# 8085_shadow.net
KiCad netlist of a schematic drawn in EAGLE
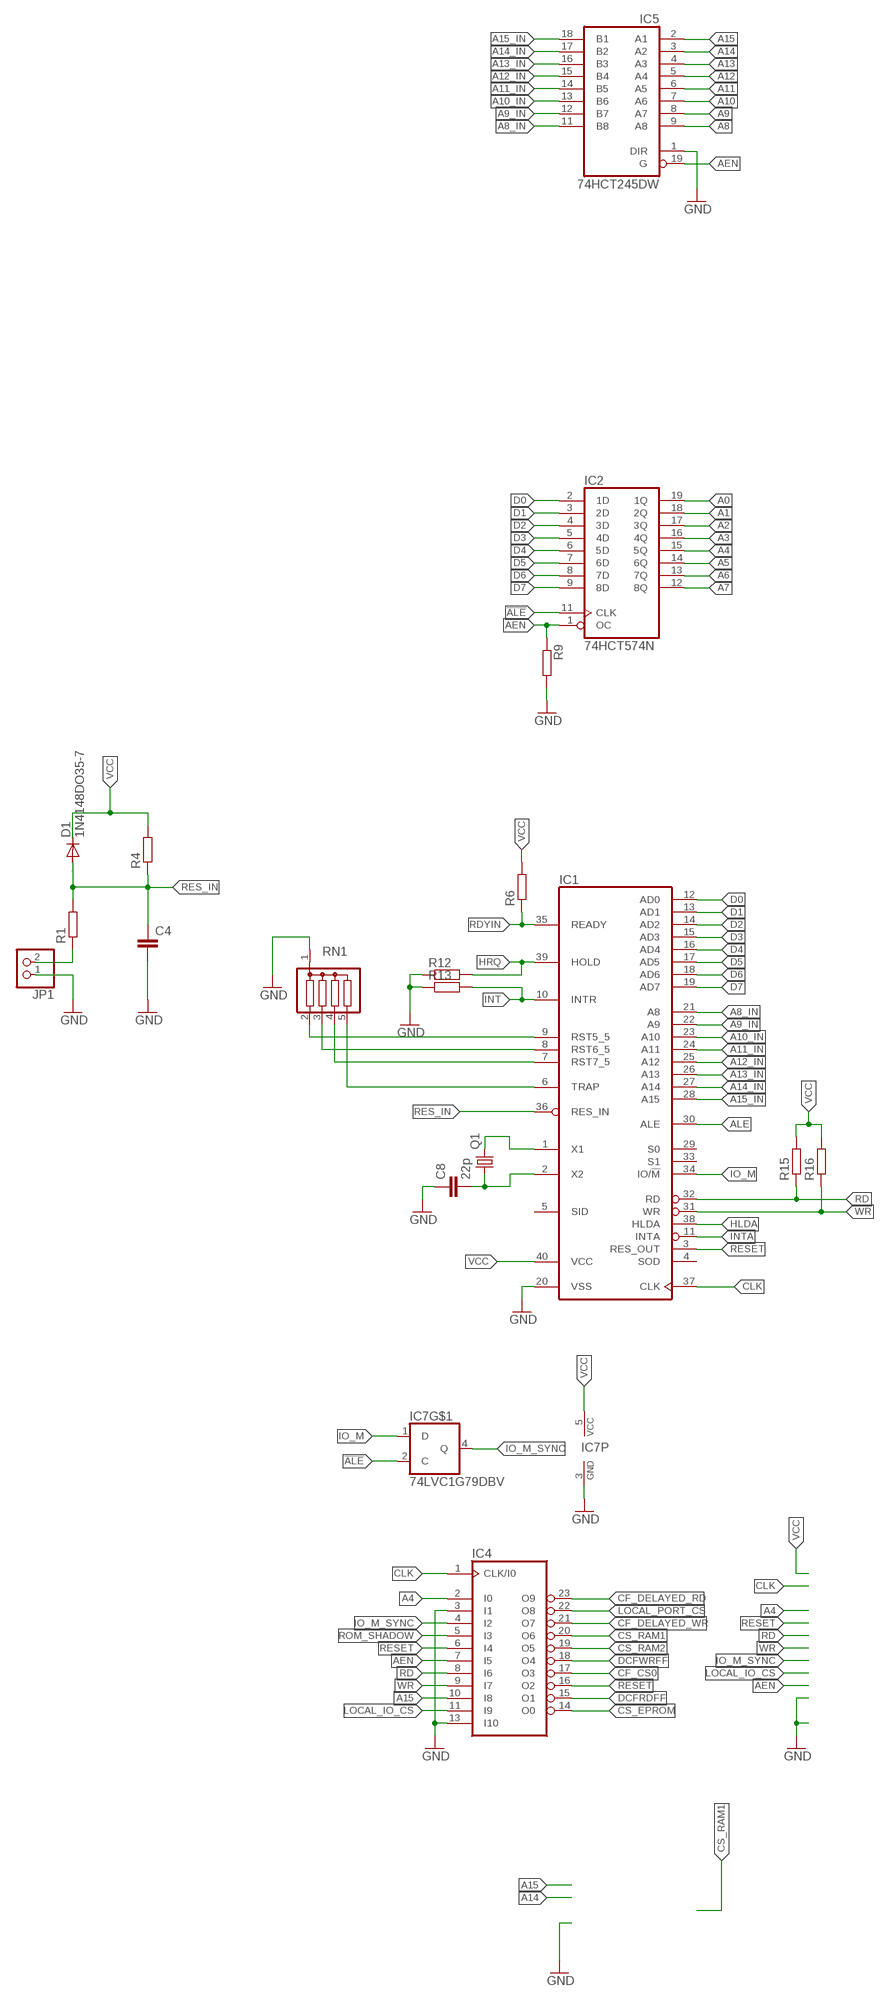
[diagram p0: schematic, sheet 1, part 1 of 3]
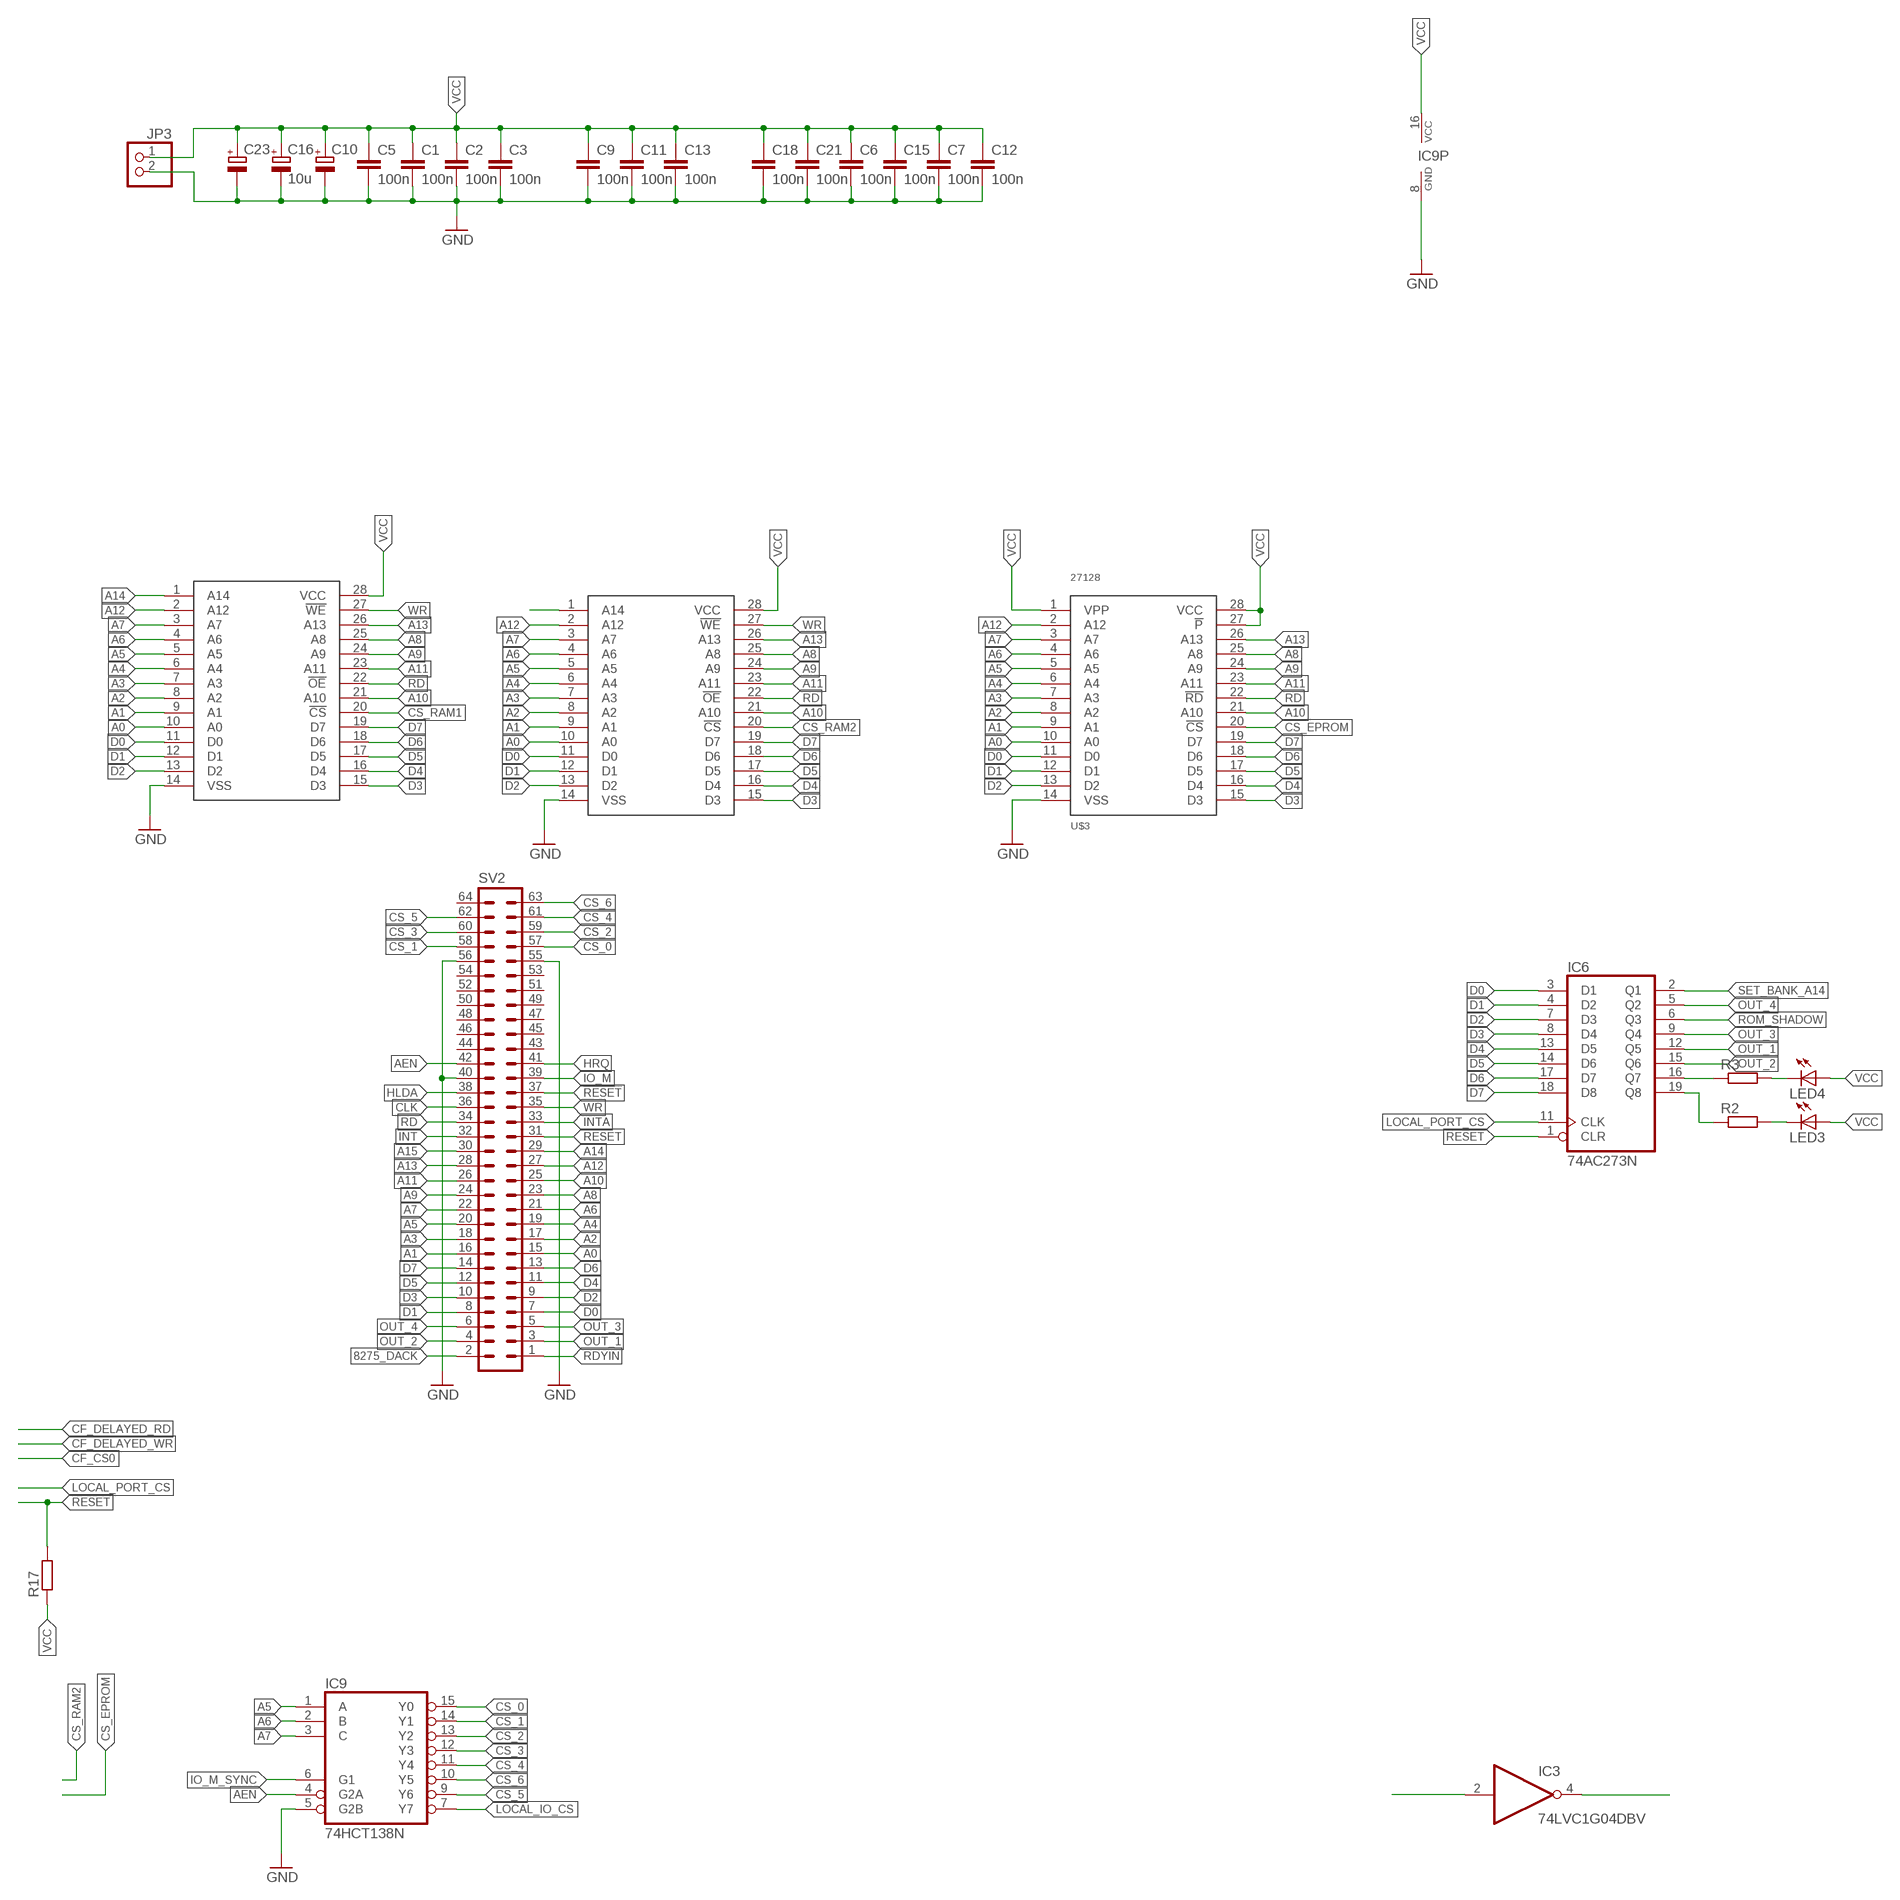
[diagram p1: schematic, sheet 1, part 2 of 3]
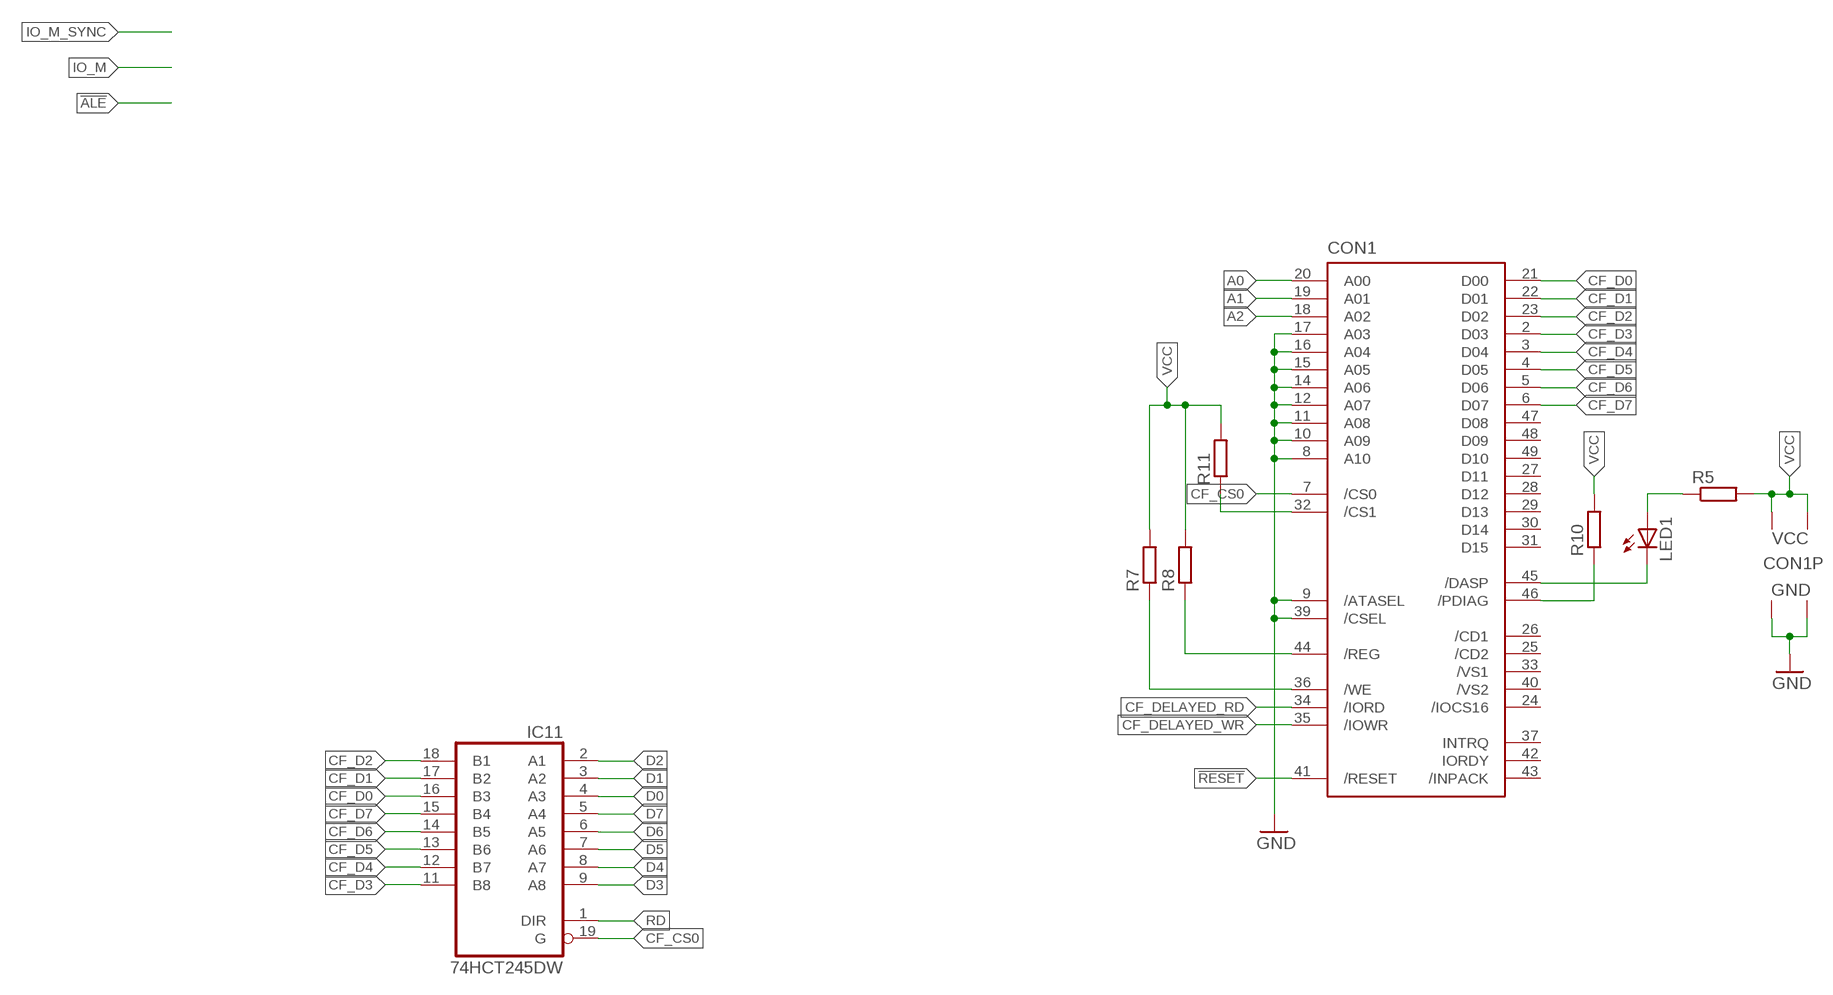
[diagram p2: schematic, sheet 1, part 3 of 3]

(export (version "E")
  (design (tool "Eeschema 10.0.6"))
  (components
    (comp (ref "C1")
      (value "100n")
      (footprint "eagle-import:C0805")
      (libsource (lib "eagle-import") (part "C-EUC0805"))
    )
    (comp (ref "C2")
      (value "100n")
      (footprint "eagle-import:C0805")
      (libsource (lib "eagle-import") (part "C-EUC0805"))
    )
    (comp (ref "C3")
      (value "100n")
      (footprint "eagle-import:C0805")
      (libsource (lib "eagle-import") (part "C-EUC0805"))
    )
    (comp (ref "C4")
      (value "C-EUC0603")
      (footprint "eagle-import:C0603")
      (libsource (lib "eagle-import") (part "C-EUC0603"))
    )
    (comp (ref "C5")
      (value "100n")
      (footprint "eagle-import:C0603")
      (libsource (lib "eagle-import") (part "C-EUC0603"))
    )
    (comp (ref "C6")
      (value "100n")
      (footprint "eagle-import:C0603")
      (libsource (lib "eagle-import") (part "C-EUC0603"))
    )
    (comp (ref "C7")
      (value "100n")
      (footprint "eagle-import:C0603")
      (libsource (lib "eagle-import") (part "C-EUC0603"))
    )
    (comp (ref "C8")
      (value "22p")
      (footprint "eagle-import:C0603")
      (libsource (lib "eagle-import") (part "C-EUC0603"))
    )
    (comp (ref "C9")
      (value "100n")
      (footprint "eagle-import:C1206")
      (libsource (lib "eagle-import") (part "C-EUC1206"))
    )
    (comp (ref "C10")
      (value "CPOL-EUE5-10.5")
      (footprint "eagle-import:E5-10,5")
      (libsource (lib "eagle-import") (part "CPOL-EUE5-10.5"))
    )
    (comp (ref "C11")
      (value "100n")
      (footprint "eagle-import:C0805")
      (libsource (lib "eagle-import") (part "C-EUC0805"))
    )
    (comp (ref "C12")
      (value "100n")
      (footprint "eagle-import:C0805")
      (libsource (lib "eagle-import") (part "C-EUC0805"))
    )
    (comp (ref "C13")
      (value "100n")
      (footprint "eagle-import:C0805")
      (libsource (lib "eagle-import") (part "C-EUC0805"))
    )
    (comp (ref "C15")
      (value "100n")
      (footprint "eagle-import:C0603")
      (libsource (lib "eagle-import") (part "C-EUC0603"))
    )
    (comp (ref "C16")
      (value "10u")
      (footprint "eagle-import:SMC_B")
      (libsource (lib "eagle-import") (part "CPOL-EUSMCB"))
    )
    (comp (ref "C18")
      (value "100n")
      (footprint "eagle-import:C0603")
      (libsource (lib "eagle-import") (part "C-EUC0603"))
    )
    (comp (ref "C21")
      (value "100n")
      (footprint "eagle-import:C0603")
      (libsource (lib "eagle-import") (part "C-EUC0603"))
    )
    (comp (ref "C23")
      (value "CPOL-EUE5-10.5")
      (footprint "eagle-import:E5-10,5")
      (libsource (lib "eagle-import") (part "CPOL-EUE5-10.5"))
    )
    (comp (ref "CON1")
      (value "CF-CARD-IDE_MODE")
      (footprint "eagle-import:MI20-50PD-SF")
      (libsource (lib "eagle-import") (part "CF-CARD-IDE_MODE"))
    )
    (comp (ref "D1")
      (value "1N4148DO35-7")
      (footprint "eagle-import:DO35-7")
      (libsource (lib "eagle-import") (part "1N4148DO35-7"))
    )
    (comp (ref "IC1")
      (value "8085")
      (footprint "eagle-import:DIL40")
      (libsource (lib "eagle-import") (part "8085"))
    )
    (comp (ref "IC2")
      (value "74HCT574N")
      (footprint "eagle-import:DIL20")
      (libsource (lib "eagle-import") (part "74574NHCT"))
    )
    (comp (ref "IC3")
      (value "74LVC1G04DBV")
      (footprint "eagle-import:SOT23-5")
      (libsource (lib "eagle-import") (part "741G04DBVLVC"))
    )
    (comp (ref "IC4")
      (value "22V10")
      (footprint "eagle-import:DIL24-3")
      (fields (field (name "MPN") "GAL22V10D-7LPN"))
      (libsource (lib "eagle-import") (part "22V10"))
    )
    (comp (ref "IC5")
      (value "74HCT245DW")
      (footprint "eagle-import:SO20W")
      (libsource (lib "eagle-import") (part "74245DWHCT"))
    )
    (comp (ref "IC6")
      (value "74AC273N")
      (footprint "eagle-import:DIL20")
      (libsource (lib "eagle-import") (part "74273NAC"))
    )
    (comp (ref "IC7")
      (value "74LVC1G79DBV")
      (footprint "eagle-import:SOT23-5")
      (libsource (lib "eagle-import") (part "741G79DBVLVC"))
    )
    (comp (ref "IC9")
      (value "74HCT138N")
      (footprint "eagle-import:DIL16")
      (libsource (lib "eagle-import") (part "74138NHCT"))
    )
    (comp (ref "IC11")
      (value "74HCT245DW")
      (footprint "eagle-import:SO20W")
      (libsource (lib "eagle-import") (part "74245DWHCT"))
    )
    (comp (ref "JP1")
      (value "PINHD-1X2")
      (footprint "eagle-import:1X02")
      (libsource (lib "eagle-import") (part "PINHD-1X2"))
    )
    (comp (ref "JP3")
      (value "PINHD-1X2")
      (footprint "eagle-import:1X02")
      (libsource (lib "eagle-import") (part "PINHD-1X2"))
    )
    (comp (ref "LED1")
      (value "LED5MM")
      (footprint "eagle-import:LED5MM")
      (libsource (lib "eagle-import") (part "LED5MM"))
    )
    (comp (ref "LED3")
      (value "LED5MM")
      (footprint "eagle-import:LED5MM")
      (libsource (lib "eagle-import") (part "LED5MM"))
    )
    (comp (ref "LED4")
      (value "LED5MM")
      (footprint "eagle-import:LED5MM")
      (libsource (lib "eagle-import") (part "LED5MM"))
    )
    (comp (ref "Q1")
      (value "CRYSTALHC49S")
      (footprint "eagle-import:HC49_S")
      (libsource (lib "eagle-import") (part "CRYSTALHC49S"))
    )
    (comp (ref "R1")
      (value "R-EU_0204/5")
      (footprint "eagle-import:0204_5")
      (libsource (lib "eagle-import") (part "R-EU_0204/5"))
    )
    (comp (ref "R2")
      (value "R-EU_R1206")
      (footprint "eagle-import:R1206")
      (libsource (lib "eagle-import") (part "R-EU_R1206"))
    )
    (comp (ref "R3")
      (value "R-EU_R1206")
      (footprint "eagle-import:R1206")
      (libsource (lib "eagle-import") (part "R-EU_R1206"))
    )
    (comp (ref "R4")
      (value "R-EU_0204/7")
      (footprint "eagle-import:0204_7")
      (libsource (lib "eagle-import") (part "R-EU_0204/7"))
    )
    (comp (ref "R5")
      (value "R-EU_R0603")
      (footprint "eagle-import:R0603")
      (libsource (lib "eagle-import") (part "R-EU_R0603"))
    )
    (comp (ref "R6")
      (value "R-EU_0204/5")
      (footprint "eagle-import:0204_5")
      (libsource (lib "eagle-import") (part "R-EU_0204/5"))
    )
    (comp (ref "R7")
      (value "R-EU_0207/10")
      (footprint "eagle-import:0207_10")
      (libsource (lib "eagle-import") (part "R-EU_0207/10"))
    )
    (comp (ref "R8")
      (value "R-EU_0207/12")
      (footprint "eagle-import:0207_12")
      (libsource (lib "eagle-import") (part "R-EU_0207/12"))
    )
    (comp (ref "R9")
      (value "R-EU_R0603")
      (footprint "eagle-import:R0603")
      (libsource (lib "eagle-import") (part "R-EU_R0603"))
    )
    (comp (ref "R10")
      (value "R-EU_0207/12")
      (footprint "eagle-import:0207_12")
      (libsource (lib "eagle-import") (part "R-EU_0207/12"))
    )
    (comp (ref "R11")
      (value "R-EU_0207/10")
      (footprint "eagle-import:0207_10")
      (libsource (lib "eagle-import") (part "R-EU_0207/10"))
    )
    (comp (ref "R12")
      (value "R-EU_R0603")
      (footprint "eagle-import:R0603")
      (libsource (lib "eagle-import") (part "R-EU_R0603"))
    )
    (comp (ref "R13")
      (value "R-EU_R0603")
      (footprint "eagle-import:R0603")
      (libsource (lib "eagle-import") (part "R-EU_R0603"))
    )
    (comp (ref "R15")
      (value "R-EU_0204/7")
      (footprint "eagle-import:0204_7")
      (libsource (lib "eagle-import") (part "R-EU_0204/7"))
    )
    (comp (ref "R16")
      (value "R-EU_0204/7")
      (footprint "eagle-import:0204_7")
      (libsource (lib "eagle-import") (part "R-EU_0204/7"))
    )
    (comp (ref "R17")
      (value "R-EU_0204/7")
      (footprint "eagle-import:0204_7")
      (libsource (lib "eagle-import") (part "R-EU_0204/7"))
    )
    (comp (ref "RN1")
      (value "G04R")
      (footprint "eagle-import:SIL5")
      (libsource (lib "eagle-import") (part "G04R"))
    )
    (comp (ref "SV2")
      (value "ML64L")
      (footprint "eagle-import:ML64L")
      (libsource (lib "eagle-import") (part "ML64L"))
    )
    (comp (ref "U$2")
      (value "62256")
      (footprint "eagle-import:DIL28-6")
      (libsource (lib "eagle-import") (part "62256"))
    )
    (comp (ref "U$3")
      (value "27128")
      (footprint "eagle-import:DIL28")
      (libsource (lib "eagle-import") (part "27128"))
    )
    (comp (ref "U$4")
      (value "62256")
      (footprint "eagle-import:DIL28-6")
      (libsource (lib "eagle-import") (part "62256"))
    )
  )
  (nets
    (net (code "1") (name "/~{ALE}") (class "Default")
      (node (ref "IC2") (pin "11") (pinfunction "CLK_11") (pintype "input"))
      (node (ref "IC3") (pin "4") (pinfunction "O_4") (pintype "output"))
      (node (ref "IC7") (pin "2") (pinfunction "C_2") (pintype "input"))
    )
    (net (code "2") (name "/~{RESET}") (class "Default")
      (node (ref "CON1") (pin "41") (pinfunction "/RESET_41") (pintype "input"))
      (node (ref "IC4") (pin "16") (pinfunction "O2_16") (pintype "bidirectional"))
      (node (ref "IC6") (pin "1") (pinfunction "CLR_1") (pintype "input"))
      (node (ref "R17") (pin "2") (pinfunction "2_2") (pintype "passive"))
      (node (ref "SV2") (pin "37") (pinfunction "37_37") (pintype "passive"))
    )
    (net (code "3") (name "8275_DACK") (class "Default")
      (node (ref "SV2") (pin "2") (pinfunction "2_2") (pintype "passive"))
    )
    (net (code "4") (name "A0") (class "Default")
      (node (ref "CON1") (pin "20") (pinfunction "A00_20") (pintype "input"))
      (node (ref "IC2") (pin "19") (pinfunction "1Q_19") (pintype "tri_state"))
      (node (ref "SV2") (pin "15") (pinfunction "15_15") (pintype "passive"))
      (node (ref "U$2") (pin "10") (pinfunction "A0_10") (pintype "bidirectional"))
      (node (ref "U$3") (pin "10") (pinfunction "A0_10") (pintype "bidirectional"))
      (node (ref "U$4") (pin "10") (pinfunction "A0_10") (pintype "bidirectional"))
    )
    (net (code "5") (name "A1") (class "Default")
      (node (ref "CON1") (pin "19") (pinfunction "A01_19") (pintype "input"))
      (node (ref "IC2") (pin "18") (pinfunction "2Q_18") (pintype "tri_state"))
      (node (ref "SV2") (pin "16") (pinfunction "16_16") (pintype "passive"))
      (node (ref "U$2") (pin "9") (pinfunction "A1_9") (pintype "bidirectional"))
      (node (ref "U$3") (pin "9") (pinfunction "A1_9") (pintype "bidirectional"))
      (node (ref "U$4") (pin "9") (pinfunction "A1_9") (pintype "bidirectional"))
    )
    (net (code "6") (name "A2") (class "Default")
      (node (ref "CON1") (pin "18") (pinfunction "A02_18") (pintype "input"))
      (node (ref "IC2") (pin "17") (pinfunction "3Q_17") (pintype "tri_state"))
      (node (ref "SV2") (pin "17") (pinfunction "17_17") (pintype "passive"))
      (node (ref "U$2") (pin "8") (pinfunction "A2_8") (pintype "bidirectional"))
      (node (ref "U$3") (pin "8") (pinfunction "A2_8") (pintype "bidirectional"))
      (node (ref "U$4") (pin "8") (pinfunction "A2_8") (pintype "bidirectional"))
    )
    (net (code "7") (name "A3") (class "Default")
      (node (ref "IC2") (pin "16") (pinfunction "4Q_16") (pintype "tri_state"))
      (node (ref "SV2") (pin "18") (pinfunction "18_18") (pintype "passive"))
      (node (ref "U$2") (pin "7") (pinfunction "A3_7") (pintype "bidirectional"))
      (node (ref "U$3") (pin "7") (pinfunction "A3_7") (pintype "bidirectional"))
      (node (ref "U$4") (pin "7") (pinfunction "A3_7") (pintype "bidirectional"))
    )
    (net (code "8") (name "A4") (class "Default")
      (node (ref "IC2") (pin "15") (pinfunction "5Q_15") (pintype "tri_state"))
      (node (ref "IC4") (pin "2") (pinfunction "I0_2") (pintype "input"))
      (node (ref "SV2") (pin "19") (pinfunction "19_19") (pintype "passive"))
      (node (ref "U$2") (pin "6") (pinfunction "A4_6") (pintype "bidirectional"))
      (node (ref "U$3") (pin "6") (pinfunction "A4_6") (pintype "bidirectional"))
      (node (ref "U$4") (pin "6") (pinfunction "A4_6") (pintype "bidirectional"))
    )
    (net (code "9") (name "A5") (class "Default")
      (node (ref "IC2") (pin "14") (pinfunction "6Q_14") (pintype "tri_state"))
      (node (ref "IC9") (pin "1") (pinfunction "A_1") (pintype "input"))
      (node (ref "SV2") (pin "20") (pinfunction "20_20") (pintype "passive"))
      (node (ref "U$2") (pin "5") (pinfunction "A5_5") (pintype "bidirectional"))
      (node (ref "U$3") (pin "5") (pinfunction "A5_5") (pintype "bidirectional"))
      (node (ref "U$4") (pin "5") (pinfunction "A5_5") (pintype "bidirectional"))
    )
    (net (code "10") (name "A6") (class "Default")
      (node (ref "IC2") (pin "13") (pinfunction "7Q_13") (pintype "tri_state"))
      (node (ref "IC9") (pin "2") (pinfunction "B_2") (pintype "input"))
      (node (ref "SV2") (pin "21") (pinfunction "21_21") (pintype "passive"))
      (node (ref "U$2") (pin "4") (pinfunction "A6_4") (pintype "bidirectional"))
      (node (ref "U$3") (pin "4") (pinfunction "A6_4") (pintype "bidirectional"))
      (node (ref "U$4") (pin "4") (pinfunction "A6_4") (pintype "bidirectional"))
    )
    (net (code "11") (name "A7") (class "Default")
      (node (ref "IC2") (pin "12") (pinfunction "8Q_12") (pintype "tri_state"))
      (node (ref "IC9") (pin "3") (pinfunction "C_3") (pintype "input"))
      (node (ref "SV2") (pin "22") (pinfunction "22_22") (pintype "passive"))
      (node (ref "U$2") (pin "3") (pinfunction "A7_3") (pintype "bidirectional"))
      (node (ref "U$3") (pin "3") (pinfunction "A7_3") (pintype "bidirectional"))
      (node (ref "U$4") (pin "3") (pinfunction "A7_3") (pintype "bidirectional"))
    )
    (net (code "12") (name "A8") (class "Default")
      (node (ref "IC5") (pin "9") (pinfunction "A8_9") (pintype "bidirectional"))
      (node (ref "SV2") (pin "23") (pinfunction "23_23") (pintype "passive"))
      (node (ref "U$2") (pin "25") (pinfunction "A8_25") (pintype "bidirectional"))
      (node (ref "U$3") (pin "25") (pinfunction "A8_25") (pintype "bidirectional"))
      (node (ref "U$4") (pin "25") (pinfunction "A8_25") (pintype "bidirectional"))
    )
    (net (code "13") (name "A8_IN") (class "Default")
      (node (ref "IC1") (pin "21") (pinfunction "A8_21") (pintype "output"))
      (node (ref "IC5") (pin "11") (pinfunction "B8_11") (pintype "bidirectional"))
    )
    (net (code "14") (name "A9") (class "Default")
      (node (ref "IC5") (pin "8") (pinfunction "A7_8") (pintype "bidirectional"))
      (node (ref "SV2") (pin "24") (pinfunction "24_24") (pintype "passive"))
      (node (ref "U$2") (pin "24") (pinfunction "A9_24") (pintype "bidirectional"))
      (node (ref "U$3") (pin "24") (pinfunction "A9_24") (pintype "bidirectional"))
      (node (ref "U$4") (pin "24") (pinfunction "A9_24") (pintype "bidirectional"))
    )
    (net (code "15") (name "A9_IN") (class "Default")
      (node (ref "IC1") (pin "22") (pinfunction "A9_22") (pintype "output"))
      (node (ref "IC5") (pin "12") (pinfunction "B7_12") (pintype "bidirectional"))
    )
    (net (code "16") (name "A10") (class "Default")
      (node (ref "IC5") (pin "7") (pinfunction "A6_7") (pintype "bidirectional"))
      (node (ref "SV2") (pin "25") (pinfunction "25_25") (pintype "passive"))
      (node (ref "U$2") (pin "21") (pinfunction "A10_21") (pintype "bidirectional"))
      (node (ref "U$3") (pin "21") (pinfunction "A10_21") (pintype "bidirectional"))
      (node (ref "U$4") (pin "21") (pinfunction "A10_21") (pintype "bidirectional"))
    )
    (net (code "17") (name "A10_IN") (class "Default")
      (node (ref "IC1") (pin "23") (pinfunction "A10_23") (pintype "output"))
      (node (ref "IC5") (pin "13") (pinfunction "B6_13") (pintype "bidirectional"))
    )
    (net (code "18") (name "A11") (class "Default")
      (node (ref "IC5") (pin "6") (pinfunction "A5_6") (pintype "bidirectional"))
      (node (ref "SV2") (pin "26") (pinfunction "26_26") (pintype "passive"))
      (node (ref "U$2") (pin "23") (pinfunction "A11_23") (pintype "bidirectional"))
      (node (ref "U$3") (pin "23") (pinfunction "A11_23") (pintype "bidirectional"))
      (node (ref "U$4") (pin "23") (pinfunction "A11_23") (pintype "bidirectional"))
    )
    (net (code "19") (name "A11_IN") (class "Default")
      (node (ref "IC1") (pin "24") (pinfunction "A11_24") (pintype "output"))
      (node (ref "IC5") (pin "14") (pinfunction "B5_14") (pintype "bidirectional"))
    )
    (net (code "20") (name "A12") (class "Default")
      (node (ref "IC5") (pin "5") (pinfunction "A4_5") (pintype "bidirectional"))
      (node (ref "SV2") (pin "27") (pinfunction "27_27") (pintype "passive"))
      (node (ref "U$2") (pin "2") (pinfunction "A12_2") (pintype "bidirectional"))
      (node (ref "U$3") (pin "2") (pinfunction "A12_2") (pintype "bidirectional"))
      (node (ref "U$4") (pin "2") (pinfunction "A12_2") (pintype "bidirectional"))
    )
    (net (code "21") (name "A12_IN") (class "Default")
      (node (ref "IC1") (pin "25") (pinfunction "A12_25") (pintype "output"))
      (node (ref "IC5") (pin "15") (pinfunction "B4_15") (pintype "bidirectional"))
    )
    (net (code "22") (name "A13") (class "Default")
      (node (ref "IC5") (pin "4") (pinfunction "A3_4") (pintype "bidirectional"))
      (node (ref "SV2") (pin "28") (pinfunction "28_28") (pintype "passive"))
      (node (ref "U$2") (pin "26") (pinfunction "A13_26") (pintype "bidirectional"))
      (node (ref "U$3") (pin "26") (pinfunction "A13_26") (pintype "bidirectional"))
      (node (ref "U$4") (pin "26") (pinfunction "A13_26") (pintype "bidirectional"))
    )
    (net (code "23") (name "A13_IN") (class "Default")
      (node (ref "IC1") (pin "26") (pinfunction "A13_26") (pintype "output"))
      (node (ref "IC5") (pin "16") (pinfunction "B3_16") (pintype "bidirectional"))
    )
    (net (code "24") (name "A14") (class "Default")
      (node (ref "IC5") (pin "3") (pinfunction "A2_3") (pintype "bidirectional"))
      (node (ref "SV2") (pin "29") (pinfunction "29_29") (pintype "passive"))
      (node (ref "U$2") (pin "1") (pinfunction "A14_1") (pintype "bidirectional"))
      (node (ref "U$4") (pin "1") (pinfunction "A14_1") (pintype "bidirectional"))
    )
    (net (code "25") (name "A14_IN") (class "Default")
      (node (ref "IC1") (pin "27") (pinfunction "A14_27") (pintype "output"))
      (node (ref "IC5") (pin "17") (pinfunction "B2_17") (pintype "bidirectional"))
    )
    (net (code "26") (name "A15") (class "Default")
      (node (ref "IC4") (pin "10") (pinfunction "I8_10") (pintype "input"))
      (node (ref "IC5") (pin "2") (pinfunction "A1_2") (pintype "bidirectional"))
      (node (ref "SV2") (pin "30") (pinfunction "30_30") (pintype "passive"))
    )
    (net (code "27") (name "A15_IN") (class "Default")
      (node (ref "IC1") (pin "28") (pinfunction "A15_28") (pintype "output"))
      (node (ref "IC5") (pin "18") (pinfunction "B1_18") (pintype "bidirectional"))
    )
    (net (code "28") (name "AEN") (class "Default")
      (node (ref "IC2") (pin "1") (pinfunction "OC_1") (pintype "input"))
      (node (ref "IC4") (pin "7") (pinfunction "I5_7") (pintype "input"))
      (node (ref "IC5") (pin "19") (pinfunction "G_19") (pintype "input"))
      (node (ref "IC9") (pin "4") (pinfunction "G2A_4") (pintype "input"))
      (node (ref "R9") (pin "1") (pinfunction "1_1") (pintype "passive"))
      (node (ref "SV2") (pin "42") (pinfunction "42_42") (pintype "passive"))
    )
    (net (code "29") (name "ALE") (class "Default")
      (node (ref "IC1") (pin "30") (pinfunction "ALE_30") (pintype "output"))
      (node (ref "IC3") (pin "2") (pinfunction "I_2") (pintype "input"))
    )
    (net (code "30") (name "CF_CS0") (class "Default")
      (node (ref "CON1") (pin "7") (pinfunction "/CS0_7") (pintype "input"))
      (node (ref "IC11") (pin "19") (pinfunction "G_19") (pintype "input"))
      (node (ref "IC4") (pin "17") (pinfunction "O3_17") (pintype "bidirectional"))
    )
    (net (code "31") (name "CF_D0") (class "Default")
      (node (ref "CON1") (pin "21") (pinfunction "D00_21") (pintype "bidirectional"))
      (node (ref "IC11") (pin "16") (pinfunction "B3_16") (pintype "bidirectional"))
    )
    (net (code "32") (name "CF_D1") (class "Default")
      (node (ref "CON1") (pin "22") (pinfunction "D01_22") (pintype "bidirectional"))
      (node (ref "IC11") (pin "17") (pinfunction "B2_17") (pintype "bidirectional"))
    )
    (net (code "33") (name "CF_D2") (class "Default")
      (node (ref "CON1") (pin "23") (pinfunction "D02_23") (pintype "bidirectional"))
      (node (ref "IC11") (pin "18") (pinfunction "B1_18") (pintype "bidirectional"))
    )
    (net (code "34") (name "CF_D3") (class "Default")
      (node (ref "CON1") (pin "2") (pinfunction "D03_2") (pintype "bidirectional"))
      (node (ref "IC11") (pin "11") (pinfunction "B8_11") (pintype "bidirectional"))
    )
    (net (code "35") (name "CF_D4") (class "Default")
      (node (ref "CON1") (pin "3") (pinfunction "D04_3") (pintype "bidirectional"))
      (node (ref "IC11") (pin "12") (pinfunction "B7_12") (pintype "bidirectional"))
    )
    (net (code "36") (name "CF_D5") (class "Default")
      (node (ref "CON1") (pin "4") (pinfunction "D05_4") (pintype "bidirectional"))
      (node (ref "IC11") (pin "13") (pinfunction "B6_13") (pintype "bidirectional"))
    )
    (net (code "37") (name "CF_D6") (class "Default")
      (node (ref "CON1") (pin "5") (pinfunction "D06_5") (pintype "bidirectional"))
      (node (ref "IC11") (pin "14") (pinfunction "B5_14") (pintype "bidirectional"))
    )
    (net (code "38") (name "CF_D7") (class "Default")
      (node (ref "CON1") (pin "6") (pinfunction "D07_6") (pintype "bidirectional"))
      (node (ref "IC11") (pin "15") (pinfunction "B4_15") (pintype "bidirectional"))
    )
    (net (code "39") (name "CF_DELAYED_RD") (class "Default")
      (node (ref "CON1") (pin "34") (pinfunction "/IORD_34") (pintype "input"))
      (node (ref "IC4") (pin "23") (pinfunction "O9_23") (pintype "bidirectional"))
    )
    (net (code "40") (name "CF_DELAYED_WR") (class "Default")
      (node (ref "CON1") (pin "35") (pinfunction "/IOWR_35") (pintype "input"))
      (node (ref "IC4") (pin "21") (pinfunction "O7_21") (pintype "bidirectional"))
    )
    (net (code "41") (name "CLK") (class "Default")
      (node (ref "IC1") (pin "37") (pinfunction "CLK_37") (pintype "output"))
      (node (ref "IC4") (pin "1") (pinfunction "CLK/I0_1") (pintype "input"))
      (node (ref "SV2") (pin "36") (pinfunction "36_36") (pintype "passive"))
    )
    (net (code "42") (name "CS_0") (class "Default")
      (node (ref "IC9") (pin "15") (pinfunction "Y0_15") (pintype "output"))
      (node (ref "SV2") (pin "57") (pinfunction "57_57") (pintype "passive"))
    )
    (net (code "43") (name "CS_1") (class "Default")
      (node (ref "IC9") (pin "14") (pinfunction "Y1_14") (pintype "output"))
      (node (ref "SV2") (pin "58") (pinfunction "58_58") (pintype "passive"))
    )
    (net (code "44") (name "CS_2") (class "Default")
      (node (ref "IC9") (pin "13") (pinfunction "Y2_13") (pintype "output"))
      (node (ref "SV2") (pin "59") (pinfunction "59_59") (pintype "passive"))
    )
    (net (code "45") (name "CS_3") (class "Default")
      (node (ref "IC9") (pin "12") (pinfunction "Y3_12") (pintype "output"))
      (node (ref "SV2") (pin "60") (pinfunction "60_60") (pintype "passive"))
    )
    (net (code "46") (name "CS_4") (class "Default")
      (node (ref "IC9") (pin "11") (pinfunction "Y4_11") (pintype "output"))
      (node (ref "SV2") (pin "61") (pinfunction "61_61") (pintype "passive"))
    )
    (net (code "47") (name "CS_5") (class "Default")
      (node (ref "IC9") (pin "9") (pinfunction "Y6_9") (pintype "output"))
      (node (ref "SV2") (pin "62") (pinfunction "62_62") (pintype "passive"))
    )
    (net (code "48") (name "CS_6") (class "Default")
      (node (ref "IC9") (pin "10") (pinfunction "Y5_10") (pintype "output"))
      (node (ref "SV2") (pin "63") (pinfunction "63_63") (pintype "passive"))
    )
    (net (code "49") (name "CS_EPROM") (class "Default")
      (node (ref "IC4") (pin "14") (pinfunction "O0_14") (pintype "bidirectional"))
      (node (ref "U$3") (pin "20") (pinfunction "~{CS}_20") (pintype "bidirectional"))
    )
    (net (code "50") (name "CS_RAM1") (class "Default")
      (node (ref "IC4") (pin "20") (pinfunction "O6_20") (pintype "bidirectional"))
      (node (ref "U$4") (pin "20") (pinfunction "~{CS}_20") (pintype "bidirectional"))
    )
    (net (code "51") (name "CS_RAM2") (class "Default")
      (node (ref "IC4") (pin "19") (pinfunction "O5_19") (pintype "bidirectional"))
      (node (ref "U$2") (pin "20") (pinfunction "~{CS}_20") (pintype "bidirectional"))
    )
    (net (code "52") (name "D0") (class "Default")
      (node (ref "IC1") (pin "12") (pinfunction "AD0_12") (pintype "bidirectional"))
      (node (ref "IC11") (pin "4") (pinfunction "A3_4") (pintype "bidirectional"))
      (node (ref "IC2") (pin "2") (pinfunction "1D_2") (pintype "input"))
      (node (ref "IC6") (pin "3") (pinfunction "D1_3") (pintype "input"))
      (node (ref "SV2") (pin "7") (pinfunction "7_7") (pintype "passive"))
      (node (ref "U$2") (pin "11") (pinfunction "D0_11") (pintype "bidirectional"))
      (node (ref "U$3") (pin "11") (pinfunction "D0_11") (pintype "bidirectional"))
      (node (ref "U$4") (pin "11") (pinfunction "D0_11") (pintype "bidirectional"))
    )
    (net (code "53") (name "D1") (class "Default")
      (node (ref "IC1") (pin "13") (pinfunction "AD1_13") (pintype "bidirectional"))
      (node (ref "IC11") (pin "3") (pinfunction "A2_3") (pintype "bidirectional"))
      (node (ref "IC2") (pin "3") (pinfunction "2D_3") (pintype "input"))
      (node (ref "IC6") (pin "4") (pinfunction "D2_4") (pintype "input"))
      (node (ref "SV2") (pin "8") (pinfunction "8_8") (pintype "passive"))
      (node (ref "U$2") (pin "12") (pinfunction "D1_12") (pintype "bidirectional"))
      (node (ref "U$3") (pin "12") (pinfunction "D1_12") (pintype "bidirectional"))
      (node (ref "U$4") (pin "12") (pinfunction "D1_12") (pintype "bidirectional"))
    )
    (net (code "54") (name "D2") (class "Default")
      (node (ref "IC1") (pin "14") (pinfunction "AD2_14") (pintype "bidirectional"))
      (node (ref "IC11") (pin "2") (pinfunction "A1_2") (pintype "bidirectional"))
      (node (ref "IC2") (pin "4") (pinfunction "3D_4") (pintype "input"))
      (node (ref "IC6") (pin "7") (pinfunction "D3_7") (pintype "input"))
      (node (ref "SV2") (pin "9") (pinfunction "9_9") (pintype "passive"))
      (node (ref "U$2") (pin "13") (pinfunction "D2_13") (pintype "bidirectional"))
      (node (ref "U$3") (pin "13") (pinfunction "D2_13") (pintype "bidirectional"))
      (node (ref "U$4") (pin "13") (pinfunction "D2_13") (pintype "bidirectional"))
    )
    (net (code "55") (name "D3") (class "Default")
      (node (ref "IC1") (pin "15") (pinfunction "AD3_15") (pintype "bidirectional"))
      (node (ref "IC11") (pin "9") (pinfunction "A8_9") (pintype "bidirectional"))
      (node (ref "IC2") (pin "5") (pinfunction "4D_5") (pintype "input"))
      (node (ref "IC6") (pin "8") (pinfunction "D4_8") (pintype "input"))
      (node (ref "SV2") (pin "10") (pinfunction "10_10") (pintype "passive"))
      (node (ref "U$2") (pin "15") (pinfunction "D3_15") (pintype "bidirectional"))
      (node (ref "U$3") (pin "15") (pinfunction "D3_15") (pintype "bidirectional"))
      (node (ref "U$4") (pin "15") (pinfunction "D3_15") (pintype "bidirectional"))
    )
    (net (code "56") (name "D4") (class "Default")
      (node (ref "IC1") (pin "16") (pinfunction "AD4_16") (pintype "bidirectional"))
      (node (ref "IC11") (pin "8") (pinfunction "A7_8") (pintype "bidirectional"))
      (node (ref "IC2") (pin "6") (pinfunction "5D_6") (pintype "input"))
      (node (ref "IC6") (pin "13") (pinfunction "D5_13") (pintype "input"))
      (node (ref "SV2") (pin "11") (pinfunction "11_11") (pintype "passive"))
      (node (ref "U$2") (pin "16") (pinfunction "D4_16") (pintype "bidirectional"))
      (node (ref "U$3") (pin "16") (pinfunction "D4_16") (pintype "bidirectional"))
      (node (ref "U$4") (pin "16") (pinfunction "D4_16") (pintype "bidirectional"))
    )
    (net (code "57") (name "D5") (class "Default")
      (node (ref "IC1") (pin "17") (pinfunction "AD5_17") (pintype "bidirectional"))
      (node (ref "IC11") (pin "7") (pinfunction "A6_7") (pintype "bidirectional"))
      (node (ref "IC2") (pin "7") (pinfunction "6D_7") (pintype "input"))
      (node (ref "IC6") (pin "14") (pinfunction "D6_14") (pintype "input"))
      (node (ref "SV2") (pin "12") (pinfunction "12_12") (pintype "passive"))
      (node (ref "U$2") (pin "17") (pinfunction "D5_17") (pintype "bidirectional"))
      (node (ref "U$3") (pin "17") (pinfunction "D5_17") (pintype "bidirectional"))
      (node (ref "U$4") (pin "17") (pinfunction "D5_17") (pintype "bidirectional"))
    )
    (net (code "58") (name "D6") (class "Default")
      (node (ref "IC1") (pin "18") (pinfunction "AD6_18") (pintype "bidirectional"))
      (node (ref "IC11") (pin "6") (pinfunction "A5_6") (pintype "bidirectional"))
      (node (ref "IC2") (pin "8") (pinfunction "7D_8") (pintype "input"))
      (node (ref "IC6") (pin "17") (pinfunction "D7_17") (pintype "input"))
      (node (ref "SV2") (pin "13") (pinfunction "13_13") (pintype "passive"))
      (node (ref "U$2") (pin "18") (pinfunction "D6_18") (pintype "bidirectional"))
      (node (ref "U$3") (pin "18") (pinfunction "D6_18") (pintype "bidirectional"))
      (node (ref "U$4") (pin "18") (pinfunction "D6_18") (pintype "bidirectional"))
    )
    (net (code "59") (name "D7") (class "Default")
      (node (ref "IC1") (pin "19") (pinfunction "AD7_19") (pintype "bidirectional"))
      (node (ref "IC11") (pin "5") (pinfunction "A4_5") (pintype "bidirectional"))
      (node (ref "IC2") (pin "9") (pinfunction "8D_9") (pintype "input"))
      (node (ref "IC6") (pin "18") (pinfunction "D8_18") (pintype "input"))
      (node (ref "SV2") (pin "14") (pinfunction "14_14") (pintype "passive"))
      (node (ref "U$2") (pin "19") (pinfunction "D7_19") (pintype "bidirectional"))
      (node (ref "U$3") (pin "19") (pinfunction "D7_19") (pintype "bidirectional"))
      (node (ref "U$4") (pin "19") (pinfunction "D7_19") (pintype "bidirectional"))
    )
    (net (code "60") (name "DCFRDFF") (class "Default")
      (node (ref "IC4") (pin "15") (pinfunction "O1_15") (pintype "bidirectional"))
    )
    (net (code "61") (name "DCFWRFF") (class "Default")
      (node (ref "IC4") (pin "18") (pinfunction "O4_18") (pintype "bidirectional"))
    )
    (net (code "62") (name "GND") (class "Default")
      (node (ref "C1") (pin "2") (pinfunction "2_2") (pintype "passive"))
      (node (ref "C10") (pin "-") (pinfunction "-_-") (pintype "passive"))
      (node (ref "C11") (pin "2") (pinfunction "2_2") (pintype "passive"))
      (node (ref "C12") (pin "2") (pinfunction "2_2") (pintype "passive"))
      (node (ref "C13") (pin "2") (pinfunction "2_2") (pintype "passive"))
      (node (ref "C15") (pin "2") (pinfunction "2_2") (pintype "passive"))
      (node (ref "C16") (pin "-") (pinfunction "-_-") (pintype "passive"))
      (node (ref "C18") (pin "2") (pinfunction "2_2") (pintype "passive"))
      (node (ref "C2") (pin "2") (pinfunction "2_2") (pintype "passive"))
      (node (ref "C21") (pin "2") (pinfunction "2_2") (pintype "passive"))
      (node (ref "C23") (pin "-") (pinfunction "-_-") (pintype "passive"))
      (node (ref "C3") (pin "2") (pinfunction "2_2") (pintype "passive"))
      (node (ref "C4") (pin "2") (pinfunction "2_2") (pintype "passive"))
      (node (ref "C5") (pin "2") (pinfunction "2_2") (pintype "passive"))
      (node (ref "C6") (pin "2") (pinfunction "2_2") (pintype "passive"))
      (node (ref "C7") (pin "2") (pinfunction "2_2") (pintype "passive"))
      (node (ref "C8") (pin "1") (pinfunction "1_1") (pintype "passive"))
      (node (ref "C9") (pin "2") (pinfunction "2_2") (pintype "passive"))
      (node (ref "CON1") (pin "1") (pinfunction "GND1_1") (pintype "power_in"))
      (node (ref "CON1") (pin "10") (pinfunction "A09_10") (pintype "input"))
      (node (ref "CON1") (pin "11") (pinfunction "A08_11") (pintype "input"))
      (node (ref "CON1") (pin "12") (pinfunction "A07_12") (pintype "input"))
      (node (ref "CON1") (pin "14") (pinfunction "A06_14") (pintype "input"))
      (node (ref "CON1") (pin "15") (pinfunction "A05_15") (pintype "input"))
      (node (ref "CON1") (pin "16") (pinfunction "A04_16") (pintype "input"))
      (node (ref "CON1") (pin "17") (pinfunction "A03_17") (pintype "input"))
      (node (ref "CON1") (pin "39") (pinfunction "/CSEL_39") (pintype "input"))
      (node (ref "CON1") (pin "50") (pinfunction "GND2_50") (pintype "power_in"))
      (node (ref "CON1") (pin "8") (pinfunction "A10_8") (pintype "input"))
      (node (ref "CON1") (pin "9") (pinfunction "/ATASEL_9") (pintype "input"))
      (node (ref "IC1") (pin "20") (pinfunction "VSS_20") (pintype "power_in"))
      (node (ref "IC4") (pin "13") (pinfunction "I10_13") (pintype "input"))
      (node (ref "IC4") (pin "3") (pinfunction "I1_3") (pintype "input"))
      (node (ref "IC5") (pin "1") (pinfunction "DIR_1") (pintype "input"))
      (node (ref "IC7") (pin "3") (pinfunction "GND_3") (pintype "power_in"))
      (node (ref "IC9") (pin "5") (pinfunction "G2B_5") (pintype "input"))
      (node (ref "IC9") (pin "8") (pinfunction "GND_8") (pintype "power_in"))
      (node (ref "JP1") (pin "1") (pinfunction "1_1") (pintype "passive"))
      (node (ref "JP3") (pin "2") (pinfunction "2_2") (pintype "passive"))
      (node (ref "R12") (pin "1") (pinfunction "1_1") (pintype "passive"))
      (node (ref "R13") (pin "1") (pinfunction "1_1") (pintype "passive"))
      (node (ref "R9") (pin "2") (pinfunction "2_2") (pintype "passive"))
      (node (ref "RN1") (pin "1") (pinfunction "1_1") (pintype "passive"))
      (node (ref "SV2") (pin "40") (pinfunction "40_40") (pintype "passive"))
      (node (ref "SV2") (pin "55") (pinfunction "55_55") (pintype "passive"))
      (node (ref "SV2") (pin "56") (pinfunction "56_56") (pintype "passive"))
      (node (ref "U$2") (pin "14") (pinfunction "VSS_14") (pintype "bidirectional"))
      (node (ref "U$3") (pin "14") (pinfunction "VSS_14") (pintype "bidirectional"))
      (node (ref "U$4") (pin "14") (pinfunction "VSS_14") (pintype "bidirectional"))
    )
    (net (code "63") (name "HLDA") (class "Default")
      (node (ref "IC1") (pin "38") (pinfunction "HLDA_38") (pintype "output"))
      (node (ref "SV2") (pin "38") (pinfunction "38_38") (pintype "passive"))
    )
    (net (code "64") (name "HRQ") (class "Default")
      (node (ref "IC1") (pin "39") (pinfunction "HOLD_39") (pintype "input"))
      (node (ref "R12") (pin "2") (pinfunction "2_2") (pintype "passive"))
      (node (ref "SV2") (pin "41") (pinfunction "41_41") (pintype "passive"))
    )
    (net (code "65") (name "INT") (class "Default")
      (node (ref "IC1") (pin "10") (pinfunction "INTR_10") (pintype "input"))
      (node (ref "R13") (pin "2") (pinfunction "2_2") (pintype "passive"))
      (node (ref "SV2") (pin "32") (pinfunction "32_32") (pintype "passive"))
    )
    (net (code "66") (name "INTA") (class "Default")
      (node (ref "IC1") (pin "11") (pinfunction "INTA_11") (pintype "output"))
      (node (ref "SV2") (pin "33") (pinfunction "33_33") (pintype "passive"))
    )
    (net (code "67") (name "IO_M") (class "Default")
      (node (ref "IC1") (pin "34") (pinfunction "IO/~{M}_34") (pintype "output"))
      (node (ref "IC7") (pin "1") (pinfunction "D_1") (pintype "input"))
      (node (ref "SV2") (pin "39") (pinfunction "39_39") (pintype "passive"))
    )
    (net (code "68") (name "IO_M_SYNC") (class "Default")
      (node (ref "IC4") (pin "4") (pinfunction "I2_4") (pintype "input"))
      (node (ref "IC7") (pin "4") (pinfunction "Q_4") (pintype "output"))
      (node (ref "IC9") (pin "6") (pinfunction "G1_6") (pintype "input"))
    )
    (net (code "69") (name "LOCAL_IO_CS") (class "Default")
      (node (ref "IC4") (pin "11") (pinfunction "I9_11") (pintype "input"))
      (node (ref "IC9") (pin "7") (pinfunction "Y7_7") (pintype "output"))
    )
    (net (code "70") (name "LOCAL_PORT_CS") (class "Default")
      (node (ref "IC4") (pin "22") (pinfunction "O8_22") (pintype "bidirectional"))
      (node (ref "IC6") (pin "11") (pinfunction "CLK_11") (pintype "input"))
    )
    (net (code "71") (name "Net-(CON1A-{slash}CS1)") (class "Default")
      (node (ref "CON1") (pin "32") (pinfunction "/CS1_32") (pintype "input"))
      (node (ref "R11") (pin "1") (pinfunction "1_1") (pintype "passive"))
    )
    (net (code "72") (name "Net-(CON1A-{slash}DASP)") (class "Default")
      (node (ref "CON1") (pin "45") (pinfunction "/DASP_45") (pintype "bidirectional"))
      (node (ref "LED1") (pin "K") (pinfunction "C_K") (pintype "passive"))
    )
    (net (code "73") (name "Net-(CON1A-{slash}PDIAG)") (class "Default")
      (node (ref "CON1") (pin "46") (pinfunction "/PDIAG_46") (pintype "bidirectional"))
      (node (ref "R10") (pin "1") (pinfunction "1_1") (pintype "passive"))
    )
    (net (code "74") (name "Net-(CON1A-{slash}REG)") (class "Default")
      (node (ref "CON1") (pin "44") (pinfunction "/REG_44") (pintype "input"))
      (node (ref "R8") (pin "1") (pinfunction "1_1") (pintype "passive"))
    )
    (net (code "75") (name "Net-(CON1A-{slash}WE)") (class "Default")
      (node (ref "CON1") (pin "36") (pinfunction "/WE_36") (pintype "input"))
      (node (ref "R7") (pin "1") (pinfunction "1_1") (pintype "passive"))
    )
    (net (code "76") (name "Net-(IC1-RST5_5)") (class "Default")
      (node (ref "IC1") (pin "9") (pinfunction "RST5_5_9") (pintype "input"))
      (node (ref "RN1") (pin "2") (pinfunction "2_2") (pintype "passive"))
    )
    (net (code "77") (name "Net-(IC1-RST6_5)") (class "Default")
      (node (ref "IC1") (pin "8") (pinfunction "RST6_5_8") (pintype "input"))
      (node (ref "RN1") (pin "3") (pinfunction "3_3") (pintype "passive"))
    )
    (net (code "78") (name "Net-(IC1-RST7_5)") (class "Default")
      (node (ref "IC1") (pin "7") (pinfunction "RST7_5_7") (pintype "input"))
      (node (ref "RN1") (pin "4") (pinfunction "4_4") (pintype "passive"))
    )
    (net (code "79") (name "Net-(IC1-TRAP)") (class "Default")
      (node (ref "IC1") (pin "6") (pinfunction "TRAP_6") (pintype "input"))
      (node (ref "RN1") (pin "5") (pinfunction "5_5") (pintype "passive"))
    )
    (net (code "80") (name "Net-(IC1-X1)") (class "Default")
      (node (ref "IC1") (pin "1") (pinfunction "X1_1") (pintype "input"))
      (node (ref "Q1") (pin "2") (pinfunction "2_2") (pintype "passive"))
    )
    (net (code "81") (name "Net-(IC1-X2)") (class "Default")
      (node (ref "C8") (pin "2") (pinfunction "2_2") (pintype "passive"))
      (node (ref "IC1") (pin "2") (pinfunction "X2_2") (pintype "input"))
      (node (ref "Q1") (pin "1") (pinfunction "1_1") (pintype "passive"))
    )
    (net (code "82") (name "Net-(IC6A-Q7)") (class "Default")
      (node (ref "IC6") (pin "16") (pinfunction "Q7_16") (pintype "output"))
      (node (ref "R3") (pin "1") (pinfunction "1_1") (pintype "passive"))
    )
    (net (code "83") (name "Net-(IC6A-Q8)") (class "Default")
      (node (ref "IC6") (pin "19") (pinfunction "Q8_19") (pintype "output"))
      (node (ref "R2") (pin "1") (pinfunction "1_1") (pintype "passive"))
    )
    (net (code "84") (name "Net-(JP1-Pad2)") (class "Default")
      (node (ref "JP1") (pin "2") (pinfunction "2_2") (pintype "passive"))
      (node (ref "R1") (pin "1") (pinfunction "1_1") (pintype "passive"))
    )
    (net (code "85") (name "Net-(LED1-PadA)") (class "Default")
      (node (ref "LED1") (pin "A") (pinfunction "A_A") (pintype "passive"))
      (node (ref "R5") (pin "1") (pinfunction "1_1") (pintype "passive"))
    )
    (net (code "86") (name "Net-(LED3-C)") (class "Default")
      (node (ref "LED3") (pin "K") (pinfunction "C_K") (pintype "passive"))
      (node (ref "R2") (pin "2") (pinfunction "2_2") (pintype "passive"))
    )
    (net (code "87") (name "Net-(LED4-C)") (class "Default")
      (node (ref "LED4") (pin "K") (pinfunction "C_K") (pintype "passive"))
      (node (ref "R3") (pin "2") (pinfunction "2_2") (pintype "passive"))
    )
    (net (code "88") (name "OUT_1") (class "Default")
      (node (ref "IC6") (pin "12") (pinfunction "Q5_12") (pintype "output"))
      (node (ref "SV2") (pin "3") (pinfunction "3_3") (pintype "passive"))
    )
    (net (code "89") (name "OUT_2") (class "Default")
      (node (ref "IC6") (pin "15") (pinfunction "Q6_15") (pintype "output"))
      (node (ref "SV2") (pin "4") (pinfunction "4_4") (pintype "passive"))
    )
    (net (code "90") (name "OUT_3") (class "Default")
      (node (ref "IC6") (pin "9") (pinfunction "Q4_9") (pintype "output"))
      (node (ref "SV2") (pin "5") (pinfunction "5_5") (pintype "passive"))
    )
    (net (code "91") (name "OUT_4") (class "Default")
      (node (ref "IC6") (pin "5") (pinfunction "Q2_5") (pintype "output"))
      (node (ref "SV2") (pin "6") (pinfunction "6_6") (pintype "passive"))
    )
    (net (code "92") (name "RD") (class "Default")
      (node (ref "IC1") (pin "32") (pinfunction "RD_32") (pintype "output"))
      (node (ref "IC11") (pin "1") (pinfunction "DIR_1") (pintype "input"))
      (node (ref "IC4") (pin "8") (pinfunction "I6_8") (pintype "input"))
      (node (ref "R15") (pin "1") (pinfunction "1_1") (pintype "passive"))
      (node (ref "SV2") (pin "34") (pinfunction "34_34") (pintype "passive"))
      (node (ref "U$2") (pin "22") (pinfunction "~{OE}_22") (pintype "bidirectional"))
      (node (ref "U$3") (pin "22") (pinfunction "~{RD}_22") (pintype "bidirectional"))
      (node (ref "U$4") (pin "22") (pinfunction "~{OE}_22") (pintype "bidirectional"))
    )
    (net (code "93") (name "RDYIN") (class "Default")
      (node (ref "IC1") (pin "35") (pinfunction "READY_35") (pintype "input"))
      (node (ref "R6") (pin "1") (pinfunction "1_1") (pintype "passive"))
      (node (ref "SV2") (pin "1") (pinfunction "1_1") (pintype "passive"))
    )
    (net (code "94") (name "RESET") (class "Default")
      (node (ref "IC1") (pin "3") (pinfunction "RES_OUT_3") (pintype "output"))
      (node (ref "IC4") (pin "6") (pinfunction "I4_6") (pintype "input"))
      (node (ref "SV2") (pin "31") (pinfunction "31_31") (pintype "passive"))
    )
    (net (code "95") (name "RES_IN") (class "Default")
      (node (ref "C4") (pin "1") (pinfunction "1_1") (pintype "passive"))
      (node (ref "D1") (pin "A") (pinfunction "A_A") (pintype "passive"))
      (node (ref "IC1") (pin "36") (pinfunction "RES_IN_36") (pintype "input"))
      (node (ref "R1") (pin "2") (pinfunction "2_2") (pintype "passive"))
      (node (ref "R4") (pin "1") (pinfunction "1_1") (pintype "passive"))
    )
    (net (code "96") (name "ROM_SHADOW") (class "Default")
      (node (ref "IC4") (pin "5") (pinfunction "I3_5") (pintype "input"))
      (node (ref "IC6") (pin "6") (pinfunction "Q3_6") (pintype "output"))
    )
    (net (code "97") (name "SET_BANK_A14") (class "Default")
      (node (ref "IC6") (pin "2") (pinfunction "Q1_2") (pintype "output"))
    )
    (net (code "98") (name "VCC") (class "Default")
      (node (ref "C1") (pin "1") (pinfunction "1_1") (pintype "passive"))
      (node (ref "C10") (pin "+") (pinfunction "+_+") (pintype "passive"))
      (node (ref "C11") (pin "1") (pinfunction "1_1") (pintype "passive"))
      (node (ref "C12") (pin "1") (pinfunction "1_1") (pintype "passive"))
      (node (ref "C13") (pin "1") (pinfunction "1_1") (pintype "passive"))
      (node (ref "C15") (pin "1") (pinfunction "1_1") (pintype "passive"))
      (node (ref "C16") (pin "+") (pinfunction "+_+") (pintype "passive"))
      (node (ref "C18") (pin "1") (pinfunction "1_1") (pintype "passive"))
      (node (ref "C2") (pin "1") (pinfunction "1_1") (pintype "passive"))
      (node (ref "C21") (pin "1") (pinfunction "1_1") (pintype "passive"))
      (node (ref "C23") (pin "+") (pinfunction "+_+") (pintype "passive"))
      (node (ref "C3") (pin "1") (pinfunction "1_1") (pintype "passive"))
      (node (ref "C5") (pin "1") (pinfunction "1_1") (pintype "passive"))
      (node (ref "C6") (pin "1") (pinfunction "1_1") (pintype "passive"))
      (node (ref "C7") (pin "1") (pinfunction "1_1") (pintype "passive"))
      (node (ref "C9") (pin "1") (pinfunction "1_1") (pintype "passive"))
      (node (ref "CON1") (pin "13") (pinfunction "VCC2_13") (pintype "power_in"))
      (node (ref "CON1") (pin "38") (pinfunction "VCC1_38") (pintype "power_in"))
      (node (ref "D1") (pin "C") (pinfunction "C_C") (pintype "passive"))
      (node (ref "IC1") (pin "40") (pinfunction "VCC_40") (pintype "power_in"))
      (node (ref "IC7") (pin "5") (pinfunction "VCC_5") (pintype "power_in"))
      (node (ref "IC9") (pin "16") (pinfunction "VCC_16") (pintype "power_in"))
      (node (ref "JP3") (pin "1") (pinfunction "1_1") (pintype "passive"))
      (node (ref "LED3") (pin "A") (pinfunction "A_A") (pintype "passive"))
      (node (ref "LED4") (pin "A") (pinfunction "A_A") (pintype "passive"))
      (node (ref "R10") (pin "2") (pinfunction "2_2") (pintype "passive"))
      (node (ref "R11") (pin "2") (pinfunction "2_2") (pintype "passive"))
      (node (ref "R15") (pin "2") (pinfunction "2_2") (pintype "passive"))
      (node (ref "R16") (pin "2") (pinfunction "2_2") (pintype "passive"))
      (node (ref "R17") (pin "1") (pinfunction "1_1") (pintype "passive"))
      (node (ref "R4") (pin "2") (pinfunction "2_2") (pintype "passive"))
      (node (ref "R5") (pin "2") (pinfunction "2_2") (pintype "passive"))
      (node (ref "R6") (pin "2") (pinfunction "2_2") (pintype "passive"))
      (node (ref "R7") (pin "2") (pinfunction "2_2") (pintype "passive"))
      (node (ref "R8") (pin "2") (pinfunction "2_2") (pintype "passive"))
      (node (ref "U$2") (pin "28") (pinfunction "VCC_28") (pintype "bidirectional"))
      (node (ref "U$3") (pin "1") (pinfunction "VPP_1") (pintype "bidirectional"))
      (node (ref "U$3") (pin "27") (pinfunction "~{P}_27") (pintype "bidirectional"))
      (node (ref "U$3") (pin "28") (pinfunction "VCC_28") (pintype "bidirectional"))
      (node (ref "U$4") (pin "28") (pinfunction "VCC_28") (pintype "bidirectional"))
    )
    (net (code "99") (name "WR") (class "Default")
      (node (ref "IC1") (pin "31") (pinfunction "WR_31") (pintype "output"))
      (node (ref "IC4") (pin "9") (pinfunction "I7_9") (pintype "input"))
      (node (ref "R16") (pin "1") (pinfunction "1_1") (pintype "passive"))
      (node (ref "SV2") (pin "35") (pinfunction "35_35") (pintype "passive"))
      (node (ref "U$2") (pin "27") (pinfunction "~{WE}_27") (pintype "bidirectional"))
      (node (ref "U$4") (pin "27") (pinfunction "~{WE}_27") (pintype "bidirectional"))
    )
    (net (code "100") (name "unconnected-(CON1A-D08-Pad47)") (class "Default")
      (node (ref "CON1") (pin "47") (pinfunction "D08_47") (pintype "bidirectional"))
    )
    (net (code "101") (name "unconnected-(CON1A-D09-Pad48)") (class "Default")
      (node (ref "CON1") (pin "48") (pinfunction "D09_48") (pintype "bidirectional"))
    )
    (net (code "102") (name "unconnected-(CON1A-D10-Pad49)") (class "Default")
      (node (ref "CON1") (pin "49") (pinfunction "D10_49") (pintype "bidirectional"))
    )
    (net (code "103") (name "unconnected-(CON1A-D11-Pad27)") (class "Default")
      (node (ref "CON1") (pin "27") (pinfunction "D11_27") (pintype "bidirectional"))
    )
    (net (code "104") (name "unconnected-(CON1A-D12-Pad28)") (class "Default")
      (node (ref "CON1") (pin "28") (pinfunction "D12_28") (pintype "bidirectional"))
    )
    (net (code "105") (name "unconnected-(CON1A-D13-Pad29)") (class "Default")
      (node (ref "CON1") (pin "29") (pinfunction "D13_29") (pintype "bidirectional"))
    )
    (net (code "106") (name "unconnected-(CON1A-D14-Pad30)") (class "Default")
      (node (ref "CON1") (pin "30") (pinfunction "D14_30") (pintype "bidirectional"))
    )
    (net (code "107") (name "unconnected-(CON1A-D15-Pad31)") (class "Default")
      (node (ref "CON1") (pin "31") (pinfunction "D15_31") (pintype "bidirectional"))
    )
    (net (code "108") (name "unconnected-(CON1A-INTRQ-Pad37)") (class "Default")
      (node (ref "CON1") (pin "37") (pinfunction "INTRQ_37") (pintype "output"))
    )
    (net (code "109") (name "unconnected-(CON1A-IORDY-Pad42)") (class "Default")
      (node (ref "CON1") (pin "42") (pinfunction "IORDY_42") (pintype "output"))
    )
    (net (code "110") (name "unconnected-(CON1A-{slash}CD1-Pad26)") (class "Default")
      (node (ref "CON1") (pin "26") (pinfunction "/CD1_26") (pintype "output"))
    )
    (net (code "111") (name "unconnected-(CON1A-{slash}CD2-Pad25)") (class "Default")
      (node (ref "CON1") (pin "25") (pinfunction "/CD2_25") (pintype "output"))
    )
    (net (code "112") (name "unconnected-(CON1A-{slash}INPACK-Pad43)") (class "Default")
      (node (ref "CON1") (pin "43") (pinfunction "/INPACK_43") (pintype "output"))
    )
    (net (code "113") (name "unconnected-(CON1A-{slash}IOCS16-Pad24)") (class "Default")
      (node (ref "CON1") (pin "24") (pinfunction "/IOCS16_24") (pintype "output"))
    )
    (net (code "114") (name "unconnected-(CON1A-{slash}VS1-Pad33)") (class "Default")
      (node (ref "CON1") (pin "33") (pinfunction "/VS1_33") (pintype "output"))
    )
    (net (code "115") (name "unconnected-(CON1A-{slash}VS2-Pad40)") (class "Default")
      (node (ref "CON1") (pin "40") (pinfunction "/VS2_40") (pintype "output"))
    )
    (net (code "116") (name "unconnected-(IC1-S0-Pad29)") (class "Default")
      (node (ref "IC1") (pin "29") (pinfunction "S0_29") (pintype "output"))
    )
    (net (code "117") (name "unconnected-(IC1-S1-Pad33)") (class "Default")
      (node (ref "IC1") (pin "33") (pinfunction "S1_33") (pintype "output"))
    )
    (net (code "118") (name "unconnected-(IC1-SID-Pad5)") (class "Default")
      (node (ref "IC1") (pin "5") (pinfunction "SID_5") (pintype "input"))
    )
    (net (code "119") (name "unconnected-(IC1-SOD-Pad4)") (class "Default")
      (node (ref "IC1") (pin "4") (pinfunction "SOD_4") (pintype "output"))
    )
    (net (code "120") (name "unconnected-(SV2-Pad43)") (class "Default")
      (node (ref "SV2") (pin "43") (pinfunction "43_43") (pintype "passive"))
    )
    (net (code "121") (name "unconnected-(SV2-Pad44)") (class "Default")
      (node (ref "SV2") (pin "44") (pinfunction "44_44") (pintype "passive"))
    )
    (net (code "122") (name "unconnected-(SV2-Pad45)") (class "Default")
      (node (ref "SV2") (pin "45") (pinfunction "45_45") (pintype "passive"))
    )
    (net (code "123") (name "unconnected-(SV2-Pad46)") (class "Default")
      (node (ref "SV2") (pin "46") (pinfunction "46_46") (pintype "passive"))
    )
    (net (code "124") (name "unconnected-(SV2-Pad47)") (class "Default")
      (node (ref "SV2") (pin "47") (pinfunction "47_47") (pintype "passive"))
    )
    (net (code "125") (name "unconnected-(SV2-Pad48)") (class "Default")
      (node (ref "SV2") (pin "48") (pinfunction "48_48") (pintype "passive"))
    )
    (net (code "126") (name "unconnected-(SV2-Pad49)") (class "Default")
      (node (ref "SV2") (pin "49") (pinfunction "49_49") (pintype "passive"))
    )
    (net (code "127") (name "unconnected-(SV2-Pad50)") (class "Default")
      (node (ref "SV2") (pin "50") (pinfunction "50_50") (pintype "passive"))
    )
    (net (code "128") (name "unconnected-(SV2-Pad51)") (class "Default")
      (node (ref "SV2") (pin "51") (pinfunction "51_51") (pintype "passive"))
    )
    (net (code "129") (name "unconnected-(SV2-Pad52)") (class "Default")
      (node (ref "SV2") (pin "52") (pinfunction "52_52") (pintype "passive"))
    )
    (net (code "130") (name "unconnected-(SV2-Pad53)") (class "Default")
      (node (ref "SV2") (pin "53") (pinfunction "53_53") (pintype "passive"))
    )
    (net (code "131") (name "unconnected-(SV2-Pad54)") (class "Default")
      (node (ref "SV2") (pin "54") (pinfunction "54_54") (pintype "passive"))
    )
    (net (code "132") (name "unconnected-(SV2-Pad64)") (class "Default")
      (node (ref "SV2") (pin "64") (pinfunction "64_64") (pintype "passive"))
    )
  )
)
